# Pi-Display.net
KiCad netlist of a schematic drawn in EAGLE
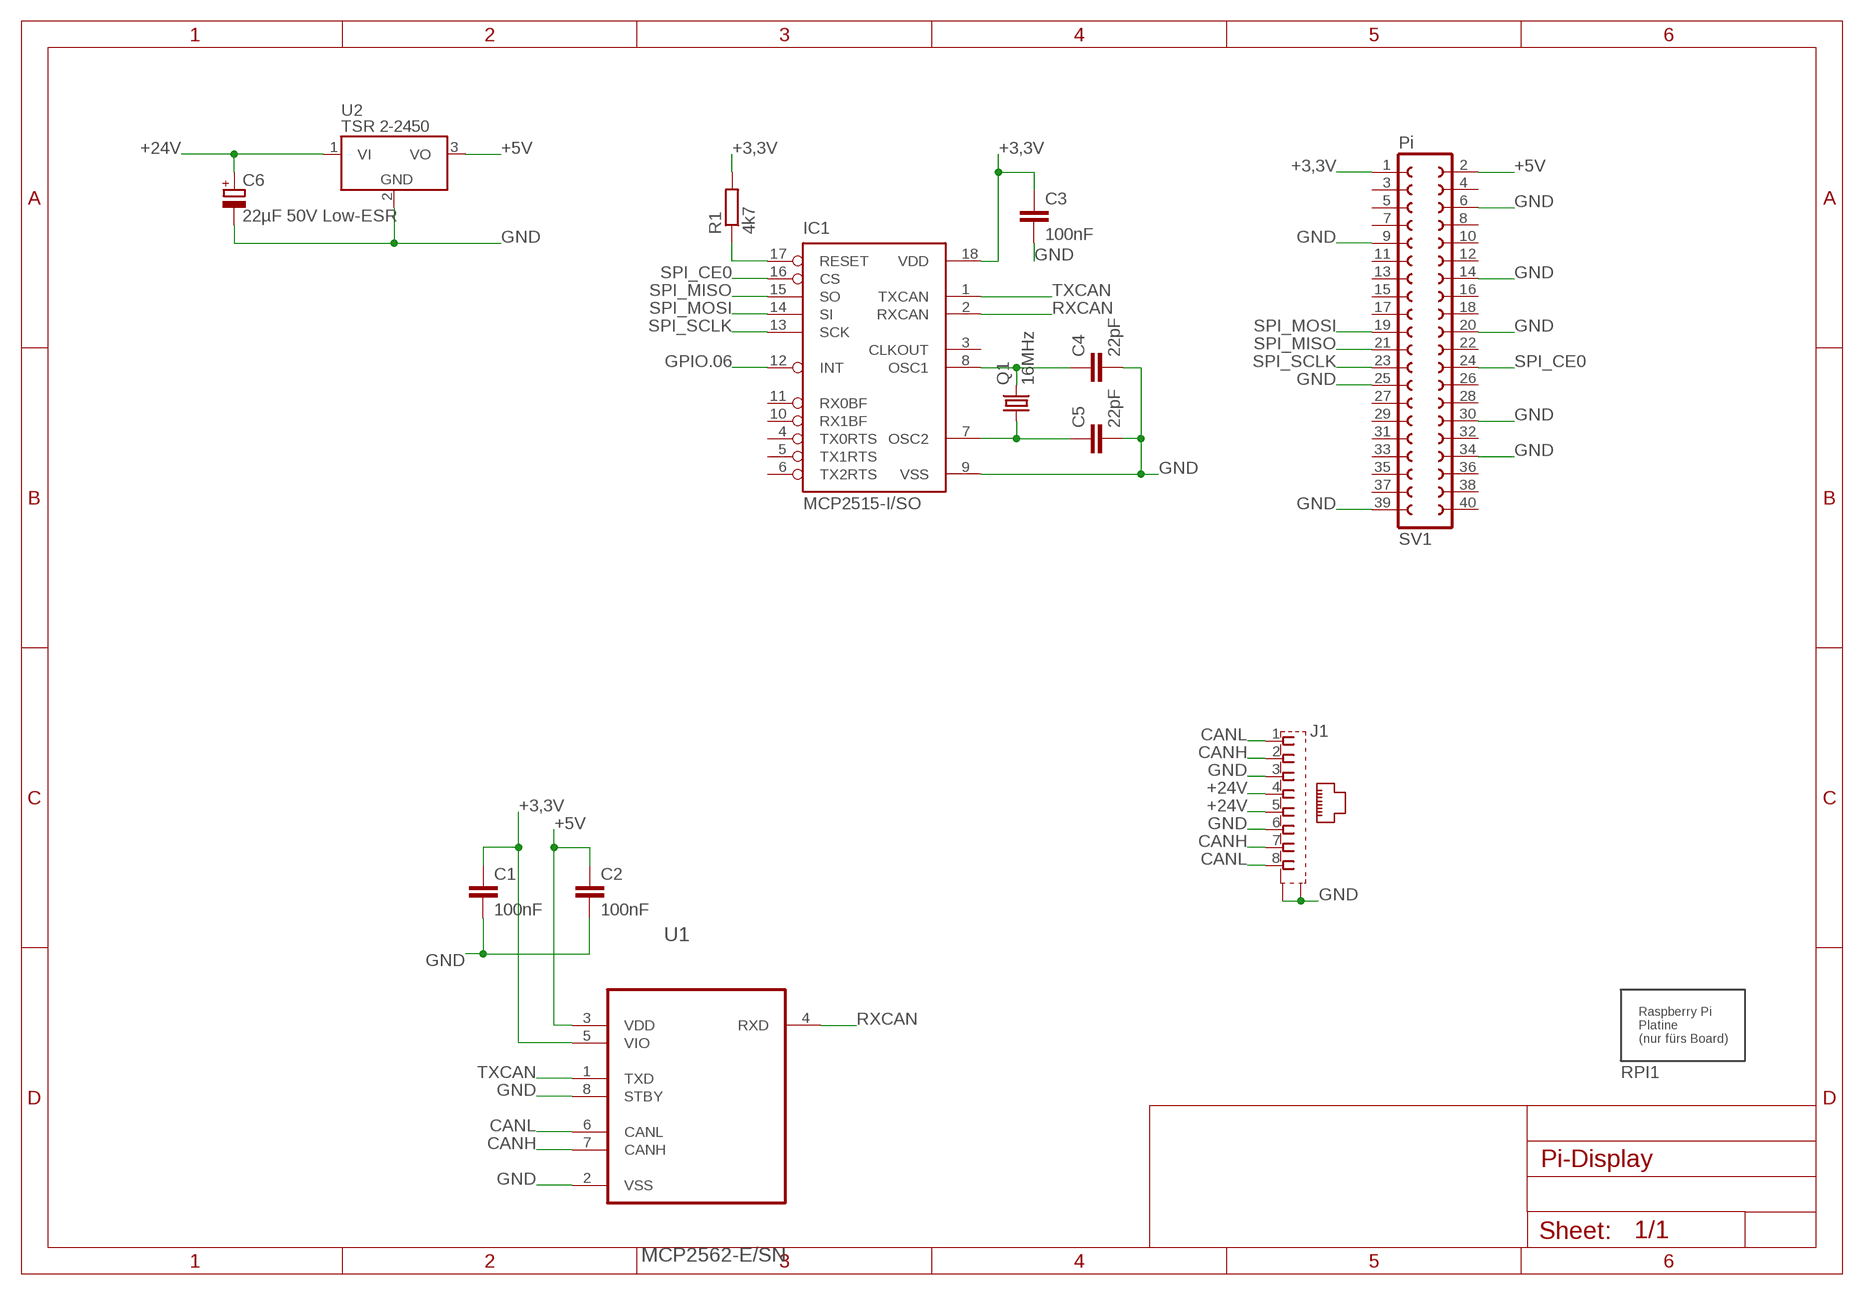
[diagram p0: schematic, sheet 1]

(export (version "E")
  (design (tool "Eeschema 10.0.6"))
  (components
    (comp (ref "C1")
      (value "100nF")
      (footprint "eagle-import:C1206")
      (libsource (lib "eagle-import") (part "C-EUC1206"))
    )
    (comp (ref "C2")
      (value "100nF")
      (footprint "eagle-import:C1206")
      (libsource (lib "eagle-import") (part "C-EUC1206"))
    )
    (comp (ref "C3")
      (value "100nF")
      (footprint "eagle-import:C1206")
      (libsource (lib "eagle-import") (part "C-EUC1206"))
    )
    (comp (ref "C4")
      (value "22pF")
      (footprint "eagle-import:C1206")
      (libsource (lib "eagle-import") (part "C-EUC1206"))
    )
    (comp (ref "C5")
      (value "22pF")
      (footprint "eagle-import:C1206")
      (libsource (lib "eagle-import") (part "C-EUC1206"))
    )
    (comp (ref "C6")
      (value "22µF 50V Low-ESR")
      (footprint "eagle-import:E2-5")
      (libsource (lib "eagle-import") (part "CPOL-EUE2-5"))
    )
    (comp (ref "IC1")
      (value "MCP2515-I/SO")
      (footprint "eagle-import:SO18L")
      (libsource (lib "eagle-import") (part "MCP2515-I/SO"))
    )
    (comp (ref "J1")
      (value "555141-1")
      (footprint "eagle-import:MEBP_8-8G")
      (libsource (lib "eagle-import") (part "555141-1"))
    )
    (comp (ref "Q1")
      (value "16MHz")
      (footprint "eagle-import:HC49UP")
      (libsource (lib "eagle-import") (part "CRYSTALHC49UP"))
    )
    (comp (ref "R1")
      (value "4k7")
      (footprint "eagle-import:R1206")
      (libsource (lib "eagle-import") (part "R-EU_R1206"))
    )
    (comp (ref "RPI1")
      (value "RASPBERRYPI-PLATINE")
      (footprint "eagle-import:RASPBERRYPI-PLATINE")
      (libsource (lib "eagle-import") (part "RASPBERRYPI-PLATINE"))
    )
    (comp (ref "SV1")
      (value "Pi")
      (footprint "eagle-import:FE20-2")
      (libsource (lib "eagle-import") (part "FE20-2"))
    )
    (comp (ref "U1")
      (value "MCP2562-E/SN")
      (footprint "eagle-import:SO08")
      (libsource (lib "eagle-import") (part "MCP2562-E/SN"))
    )
    (comp (ref "U2")
      (value "TSR 2-2450")
      (footprint "eagle-import:TSR-1")
      (libsource (lib "eagle-import") (part "TSR_1-2450"))
    )
  )
  (nets
    (net (code "1") (name "/+3,3V") (class "Default")
      (node (ref "C1") (pin "1") (pinfunction "1_1") (pintype "passive"))
      (node (ref "C3") (pin "1") (pinfunction "1_1") (pintype "passive"))
      (node (ref "IC1") (pin "18") (pinfunction "VDD_18") (pintype "power_in"))
      (node (ref "R1") (pin "2") (pinfunction "2_2") (pintype "passive"))
      (node (ref "SV1") (pin "1") (pinfunction "1_1") (pintype "passive"))
      (node (ref "U1") (pin "5") (pinfunction "VIO_5") (pintype "power_in"))
    )
    (net (code "2") (name "/+5V") (class "Default")
      (node (ref "C2") (pin "1") (pinfunction "1_1") (pintype "passive"))
      (node (ref "SV1") (pin "2") (pinfunction "2_2") (pintype "passive"))
      (node (ref "U1") (pin "3") (pinfunction "VDD_3") (pintype "power_in"))
      (node (ref "U2") (pin "3") (pinfunction "VO_3") (pintype "power_in"))
    )
    (net (code "3") (name "/+24V") (class "Default")
      (node (ref "C6") (pin "+") (pinfunction "+_+") (pintype "passive"))
      (node (ref "J1") (pin "4") (pinfunction "4_4") (pintype "passive"))
      (node (ref "J1") (pin "5") (pinfunction "5_5") (pintype "passive"))
      (node (ref "U2") (pin "1") (pinfunction "VI_1") (pintype "power_in"))
    )
    (net (code "4") (name "/CANH") (class "Default")
      (node (ref "J1") (pin "2") (pinfunction "2_2") (pintype "passive"))
      (node (ref "J1") (pin "7") (pinfunction "7_7") (pintype "passive"))
      (node (ref "U1") (pin "7") (pinfunction "CANH_7") (pintype "bidirectional"))
    )
    (net (code "5") (name "/CANL") (class "Default")
      (node (ref "J1") (pin "1") (pinfunction "1_1") (pintype "passive"))
      (node (ref "J1") (pin "8") (pinfunction "8_8") (pintype "passive"))
      (node (ref "U1") (pin "6") (pinfunction "CANL_6") (pintype "bidirectional"))
    )
    (net (code "6") (name "/GND") (class "Default")
      (node (ref "C1") (pin "2") (pinfunction "2_2") (pintype "passive"))
      (node (ref "C2") (pin "2") (pinfunction "2_2") (pintype "passive"))
      (node (ref "C3") (pin "2") (pinfunction "2_2") (pintype "passive"))
      (node (ref "C4") (pin "2") (pinfunction "2_2") (pintype "passive"))
      (node (ref "C5") (pin "2") (pinfunction "2_2") (pintype "passive"))
      (node (ref "C6") (pin "-") (pinfunction "-_-") (pintype "passive"))
      (node (ref "IC1") (pin "9") (pinfunction "VSS_9") (pintype "power_in"))
      (node (ref "J1") (pin "3") (pinfunction "3_3") (pintype "passive"))
      (node (ref "J1") (pin "6") (pinfunction "6_6") (pintype "passive"))
      (node (ref "J1") (pin "G1") (pinfunction "S1_G1") (pintype "passive"))
      (node (ref "J1") (pin "G2") (pinfunction "S2_G2") (pintype "passive"))
      (node (ref "SV1") (pin "14") (pinfunction "14_14") (pintype "passive"))
      (node (ref "SV1") (pin "20") (pinfunction "20_20") (pintype "passive"))
      (node (ref "SV1") (pin "25") (pinfunction "25_25") (pintype "passive"))
      (node (ref "SV1") (pin "30") (pinfunction "30_30") (pintype "passive"))
      (node (ref "SV1") (pin "34") (pinfunction "34_34") (pintype "passive"))
      (node (ref "SV1") (pin "39") (pinfunction "39_39") (pintype "passive"))
      (node (ref "SV1") (pin "6") (pinfunction "6_6") (pintype "passive"))
      (node (ref "SV1") (pin "9") (pinfunction "9_9") (pintype "passive"))
      (node (ref "U1") (pin "2") (pinfunction "VSS_2") (pintype "power_in"))
      (node (ref "U1") (pin "8") (pinfunction "STBY_8") (pintype "input"))
      (node (ref "U2") (pin "2") (pinfunction "GND_2") (pintype "power_in"))
    )
    (net (code "7") (name "/GPIO.06") (class "Default")
      (node (ref "IC1") (pin "12") (pinfunction "INT_12") (pintype "output"))
    )
    (net (code "8") (name "/RXCAN") (class "Default")
      (node (ref "IC1") (pin "2") (pinfunction "RXCAN_2") (pintype "input"))
      (node (ref "U1") (pin "4") (pinfunction "RXD_4") (pintype "output"))
    )
    (net (code "9") (name "/SPI_CE0") (class "Default")
      (node (ref "IC1") (pin "16") (pinfunction "CS_16") (pintype "input"))
      (node (ref "SV1") (pin "24") (pinfunction "24_24") (pintype "passive"))
    )
    (net (code "10") (name "/SPI_MISO") (class "Default")
      (node (ref "IC1") (pin "15") (pinfunction "SO_15") (pintype "output"))
      (node (ref "SV1") (pin "21") (pinfunction "21_21") (pintype "passive"))
    )
    (net (code "11") (name "/SPI_MOSI") (class "Default")
      (node (ref "IC1") (pin "14") (pinfunction "SI_14") (pintype "input"))
      (node (ref "SV1") (pin "19") (pinfunction "19_19") (pintype "passive"))
    )
    (net (code "12") (name "/SPI_SCLK") (class "Default")
      (node (ref "IC1") (pin "13") (pinfunction "SCK_13") (pintype "input"))
      (node (ref "SV1") (pin "23") (pinfunction "23_23") (pintype "passive"))
    )
    (net (code "13") (name "/TXCAN") (class "Default")
      (node (ref "IC1") (pin "1") (pinfunction "TXCAN_1") (pintype "output"))
      (node (ref "U1") (pin "1") (pinfunction "TXD_1") (pintype "input"))
    )
    (net (code "14") (name "Net-(IC1-OSC1)") (class "Default")
      (node (ref "C4") (pin "1") (pinfunction "1_1") (pintype "passive"))
      (node (ref "IC1") (pin "8") (pinfunction "OSC1_8") (pintype "input"))
      (node (ref "Q1") (pin "2") (pinfunction "2_2") (pintype "passive"))
    )
    (net (code "15") (name "Net-(IC1-OSC2)") (class "Default")
      (node (ref "C5") (pin "1") (pinfunction "1_1") (pintype "passive"))
      (node (ref "IC1") (pin "7") (pinfunction "OSC2_7") (pintype "output"))
      (node (ref "Q1") (pin "1") (pinfunction "1_1") (pintype "passive"))
    )
    (net (code "16") (name "Net-(IC1-RESET)") (class "Default")
      (node (ref "IC1") (pin "17") (pinfunction "RESET_17") (pintype "input"))
      (node (ref "R1") (pin "1") (pinfunction "1_1") (pintype "passive"))
    )
    (net (code "17") (name "unconnected-(IC1-CLKOUT-Pad3)") (class "Default")
      (node (ref "IC1") (pin "3") (pinfunction "CLKOUT_3") (pintype "output"))
    )
    (net (code "18") (name "unconnected-(IC1-RX0BF-Pad11)") (class "Default")
      (node (ref "IC1") (pin "11") (pinfunction "RX0BF_11") (pintype "output"))
    )
    (net (code "19") (name "unconnected-(IC1-RX1BF-Pad10)") (class "Default")
      (node (ref "IC1") (pin "10") (pinfunction "RX1BF_10") (pintype "output"))
    )
    (net (code "20") (name "unconnected-(IC1-TX0RTS-Pad4)") (class "Default")
      (node (ref "IC1") (pin "4") (pinfunction "TX0RTS_4") (pintype "input"))
    )
    (net (code "21") (name "unconnected-(IC1-TX1RTS-Pad5)") (class "Default")
      (node (ref "IC1") (pin "5") (pinfunction "TX1RTS_5") (pintype "input"))
    )
    (net (code "22") (name "unconnected-(IC1-TX2RTS-Pad6)") (class "Default")
      (node (ref "IC1") (pin "6") (pinfunction "TX2RTS_6") (pintype "input"))
    )
    (net (code "23") (name "unconnected-(SV1-Pad3)") (class "Default")
      (node (ref "SV1") (pin "3") (pinfunction "3_3") (pintype "passive"))
    )
    (net (code "24") (name "unconnected-(SV1-Pad4)") (class "Default")
      (node (ref "SV1") (pin "4") (pinfunction "4_4") (pintype "passive"))
    )
    (net (code "25") (name "unconnected-(SV1-Pad5)") (class "Default")
      (node (ref "SV1") (pin "5") (pinfunction "5_5") (pintype "passive"))
    )
    (net (code "26") (name "unconnected-(SV1-Pad7)") (class "Default")
      (node (ref "SV1") (pin "7") (pinfunction "7_7") (pintype "passive"))
    )
    (net (code "27") (name "unconnected-(SV1-Pad8)") (class "Default")
      (node (ref "SV1") (pin "8") (pinfunction "8_8") (pintype "passive"))
    )
    (net (code "28") (name "unconnected-(SV1-Pad10)") (class "Default")
      (node (ref "SV1") (pin "10") (pinfunction "10_10") (pintype "passive"))
    )
    (net (code "29") (name "unconnected-(SV1-Pad11)") (class "Default")
      (node (ref "SV1") (pin "11") (pinfunction "11_11") (pintype "passive"))
    )
    (net (code "30") (name "unconnected-(SV1-Pad12)") (class "Default")
      (node (ref "SV1") (pin "12") (pinfunction "12_12") (pintype "passive"))
    )
    (net (code "31") (name "unconnected-(SV1-Pad13)") (class "Default")
      (node (ref "SV1") (pin "13") (pinfunction "13_13") (pintype "passive"))
    )
    (net (code "32") (name "unconnected-(SV1-Pad15)") (class "Default")
      (node (ref "SV1") (pin "15") (pinfunction "15_15") (pintype "passive"))
    )
    (net (code "33") (name "unconnected-(SV1-Pad16)") (class "Default")
      (node (ref "SV1") (pin "16") (pinfunction "16_16") (pintype "passive"))
    )
    (net (code "34") (name "unconnected-(SV1-Pad17)") (class "Default")
      (node (ref "SV1") (pin "17") (pinfunction "17_17") (pintype "passive"))
    )
    (net (code "35") (name "unconnected-(SV1-Pad18)") (class "Default")
      (node (ref "SV1") (pin "18") (pinfunction "18_18") (pintype "passive"))
    )
    (net (code "36") (name "unconnected-(SV1-Pad22)") (class "Default")
      (node (ref "SV1") (pin "22") (pinfunction "22_22") (pintype "passive"))
    )
    (net (code "37") (name "unconnected-(SV1-Pad26)") (class "Default")
      (node (ref "SV1") (pin "26") (pinfunction "26_26") (pintype "passive"))
    )
    (net (code "38") (name "unconnected-(SV1-Pad27)") (class "Default")
      (node (ref "SV1") (pin "27") (pinfunction "27_27") (pintype "passive"))
    )
    (net (code "39") (name "unconnected-(SV1-Pad28)") (class "Default")
      (node (ref "SV1") (pin "28") (pinfunction "28_28") (pintype "passive"))
    )
    (net (code "40") (name "unconnected-(SV1-Pad29)") (class "Default")
      (node (ref "SV1") (pin "29") (pinfunction "29_29") (pintype "passive"))
    )
    (net (code "41") (name "unconnected-(SV1-Pad31)") (class "Default")
      (node (ref "SV1") (pin "31") (pinfunction "31_31") (pintype "passive"))
    )
    (net (code "42") (name "unconnected-(SV1-Pad32)") (class "Default")
      (node (ref "SV1") (pin "32") (pinfunction "32_32") (pintype "passive"))
    )
    (net (code "43") (name "unconnected-(SV1-Pad33)") (class "Default")
      (node (ref "SV1") (pin "33") (pinfunction "33_33") (pintype "passive"))
    )
    (net (code "44") (name "unconnected-(SV1-Pad35)") (class "Default")
      (node (ref "SV1") (pin "35") (pinfunction "35_35") (pintype "passive"))
    )
    (net (code "45") (name "unconnected-(SV1-Pad36)") (class "Default")
      (node (ref "SV1") (pin "36") (pinfunction "36_36") (pintype "passive"))
    )
    (net (code "46") (name "unconnected-(SV1-Pad37)") (class "Default")
      (node (ref "SV1") (pin "37") (pinfunction "37_37") (pintype "passive"))
    )
    (net (code "47") (name "unconnected-(SV1-Pad38)") (class "Default")
      (node (ref "SV1") (pin "38") (pinfunction "38_38") (pintype "passive"))
    )
    (net (code "48") (name "unconnected-(SV1-Pad40)") (class "Default")
      (node (ref "SV1") (pin "40") (pinfunction "40_40") (pintype "passive"))
    )
  )
)
